# RGBS_to_YPbPr.net
KiCad netlist of a schematic drawn in EAGLE
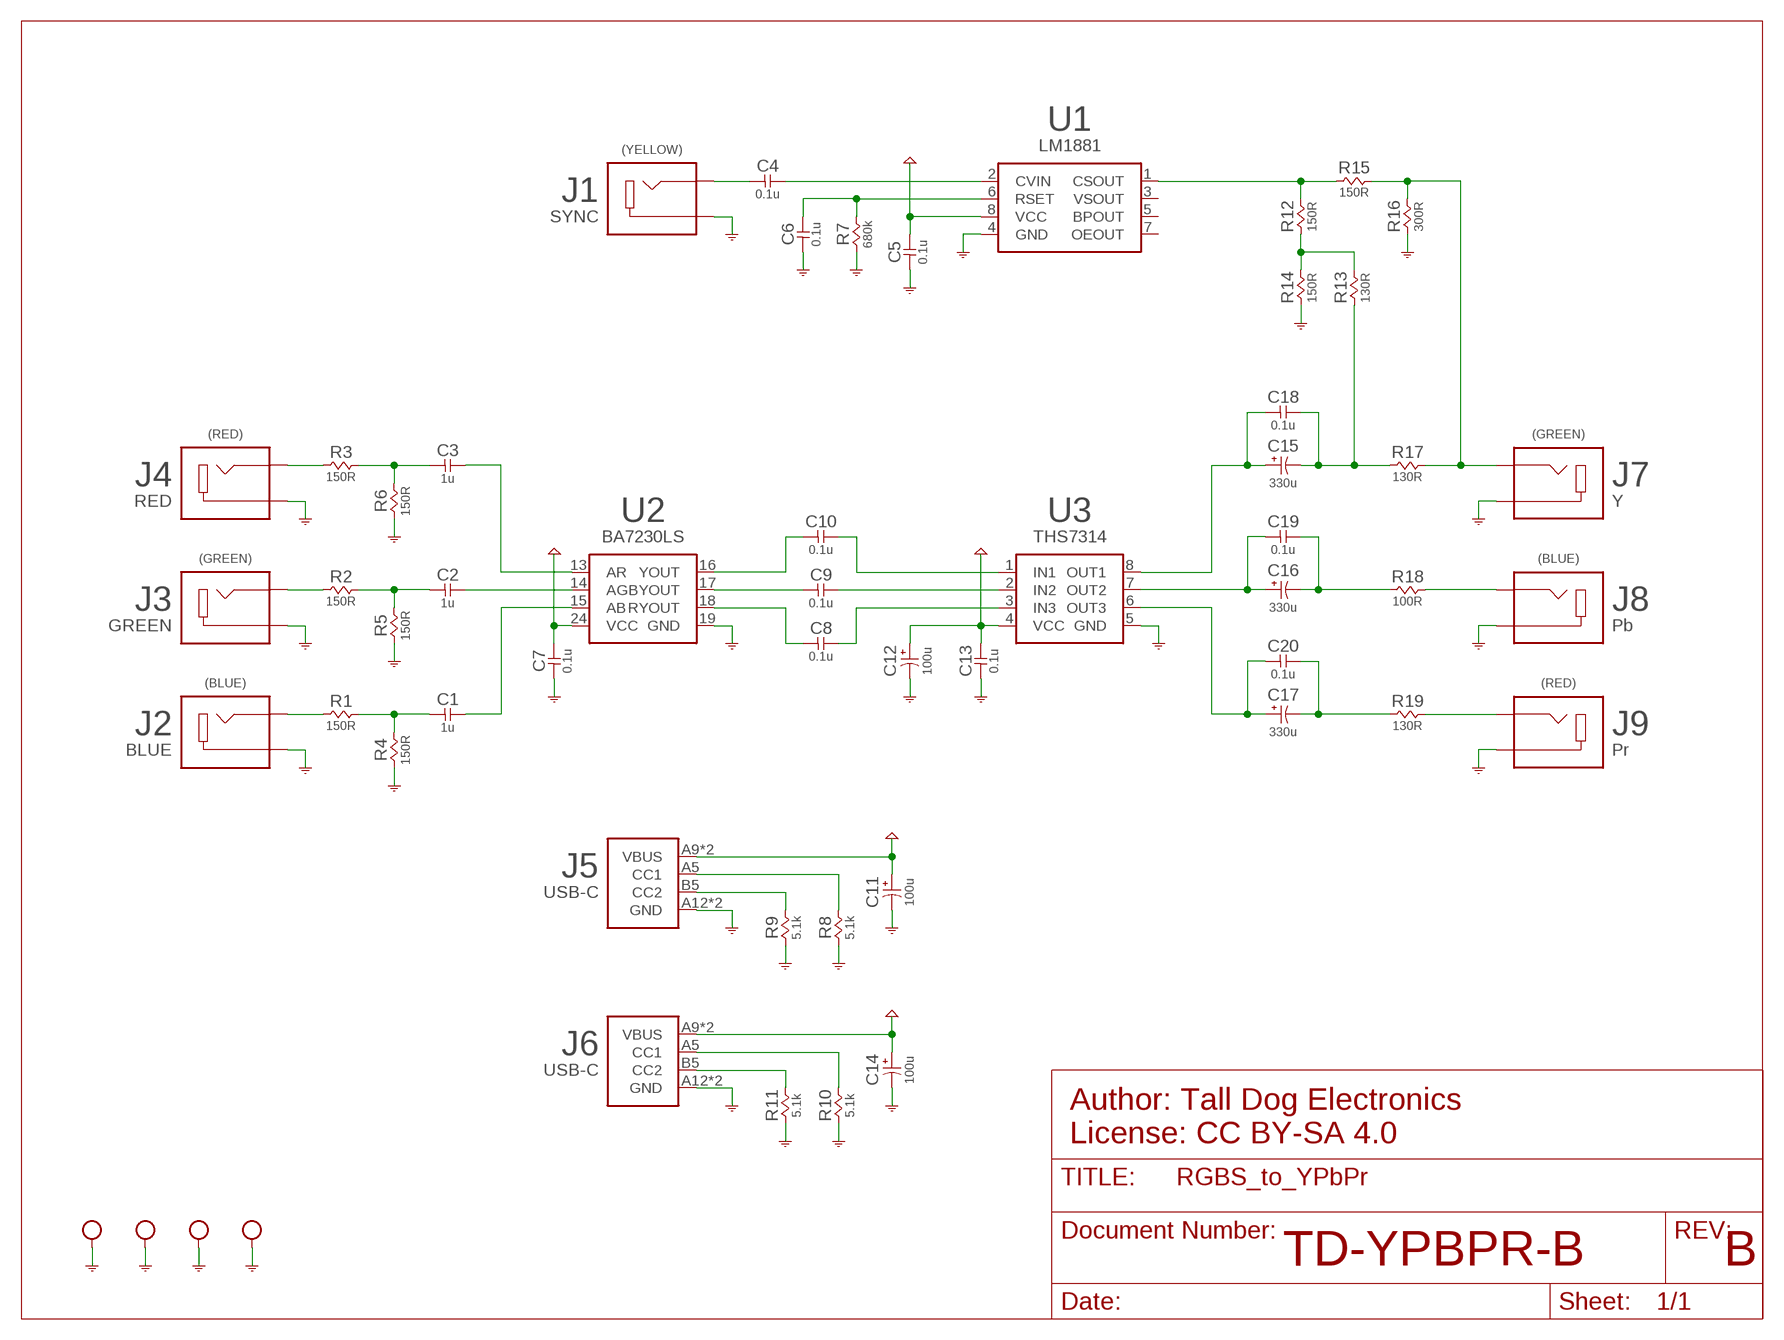
[diagram p0: schematic, sheet 1]

(export (version "E")
  (design (tool "Eeschema 10.0.6"))
  (components
    (comp (ref "C1")
      (value "1u")
      (footprint "eagle-import:0805-NP")
      (libsource (lib "eagle-import") (part "CAP-NP-0805"))
    )
    (comp (ref "C2")
      (value "1u")
      (footprint "eagle-import:0805-NP")
      (libsource (lib "eagle-import") (part "CAP-NP-0805"))
    )
    (comp (ref "C3")
      (value "1u")
      (footprint "eagle-import:0805-NP")
      (libsource (lib "eagle-import") (part "CAP-NP-0805"))
    )
    (comp (ref "C4")
      (value "0.1u")
      (footprint "eagle-import:0805-NP")
      (libsource (lib "eagle-import") (part "CAP-NP-0805"))
    )
    (comp (ref "C5")
      (value "0.1u")
      (footprint "eagle-import:0805-NP")
      (libsource (lib "eagle-import") (part "CAP-NP-0805"))
    )
    (comp (ref "C6")
      (value "0.1u")
      (footprint "eagle-import:0805-NP")
      (libsource (lib "eagle-import") (part "CAP-NP-0805"))
    )
    (comp (ref "C7")
      (value "0.1u")
      (footprint "eagle-import:0805-NP")
      (libsource (lib "eagle-import") (part "CAP-NP-0805"))
    )
    (comp (ref "C8")
      (value "0.1u")
      (footprint "eagle-import:0805-NP")
      (libsource (lib "eagle-import") (part "CAP-NP-0805"))
    )
    (comp (ref "C9")
      (value "0.1u")
      (footprint "eagle-import:0805-NP")
      (libsource (lib "eagle-import") (part "CAP-NP-0805"))
    )
    (comp (ref "C10")
      (value "0.1u")
      (footprint "eagle-import:0805-NP")
      (libsource (lib "eagle-import") (part "CAP-NP-0805"))
    )
    (comp (ref "C11")
      (value "100u")
      (footprint "eagle-import:ECAP-D")
      (libsource (lib "eagle-import") (part "CAP-P-D"))
    )
    (comp (ref "C12")
      (value "100u")
      (footprint "eagle-import:ECAP-D")
      (libsource (lib "eagle-import") (part "CAP-P-D"))
    )
    (comp (ref "C13")
      (value "0.1u")
      (footprint "eagle-import:0805-NP")
      (libsource (lib "eagle-import") (part "CAP-NP-0805"))
    )
    (comp (ref "C14")
      (value "100u")
      (footprint "eagle-import:ECAP-D")
      (libsource (lib "eagle-import") (part "CAP-P-D"))
    )
    (comp (ref "C15")
      (value "330u")
      (footprint "eagle-import:ECAP-E")
      (libsource (lib "eagle-import") (part "CAP-P-E"))
    )
    (comp (ref "C16")
      (value "330u")
      (footprint "eagle-import:ECAP-E")
      (libsource (lib "eagle-import") (part "CAP-P-E"))
    )
    (comp (ref "C17")
      (value "330u")
      (footprint "eagle-import:ECAP-E")
      (libsource (lib "eagle-import") (part "CAP-P-E"))
    )
    (comp (ref "C18")
      (value "0.1u")
      (footprint "eagle-import:0805-NP")
      (libsource (lib "eagle-import") (part "CAP-NP-0805"))
    )
    (comp (ref "C19")
      (value "0.1u")
      (footprint "eagle-import:0805-NP")
      (libsource (lib "eagle-import") (part "CAP-NP-0805"))
    )
    (comp (ref "C20")
      (value "0.1u")
      (footprint "eagle-import:0805-NP")
      (libsource (lib "eagle-import") (part "CAP-NP-0805"))
    )
    (comp (ref "HOLE1")
      (value "HOLE-M2.5")
      (footprint "eagle-import:HOLE-M2.5")
      (libsource (lib "eagle-import") (part "HOLE-M2.5"))
    )
    (comp (ref "HOLE2")
      (value "HOLE-M2.5")
      (footprint "eagle-import:HOLE-M2.5")
      (libsource (lib "eagle-import") (part "HOLE-M2.5"))
    )
    (comp (ref "HOLE3")
      (value "HOLE-M2.5")
      (footprint "eagle-import:HOLE-M2.5")
      (libsource (lib "eagle-import") (part "HOLE-M2.5"))
    )
    (comp (ref "HOLE4")
      (value "HOLE-M2.5")
      (footprint "eagle-import:HOLE-M2.5")
      (libsource (lib "eagle-import") (part "HOLE-M2.5"))
    )
    (comp (ref "J1")
      (value "SYNC")
      (footprint "eagle-import:RCJ")
      (libsource (lib "eagle-import") (part "JACK"))
    )
    (comp (ref "J2")
      (value "BLUE")
      (footprint "eagle-import:RCJ")
      (libsource (lib "eagle-import") (part "JACK"))
    )
    (comp (ref "J3")
      (value "GREEN")
      (footprint "eagle-import:RCJ")
      (libsource (lib "eagle-import") (part "JACK"))
    )
    (comp (ref "J4")
      (value "RED")
      (footprint "eagle-import:RCJ")
      (libsource (lib "eagle-import") (part "JACK"))
    )
    (comp (ref "J5")
      (value "USB-C")
      (footprint "eagle-import:USB4125")
      (libsource (lib "eagle-import") (part "USB-C-POWER"))
    )
    (comp (ref "J6")
      (value "USB-C")
      (footprint "eagle-import:USB4125")
      (libsource (lib "eagle-import") (part "USB-C-POWER"))
    )
    (comp (ref "J7")
      (value "Y")
      (footprint "eagle-import:RCJ")
      (libsource (lib "eagle-import") (part "JACK"))
    )
    (comp (ref "J8")
      (value "Pb")
      (footprint "eagle-import:RCJ")
      (libsource (lib "eagle-import") (part "JACK"))
    )
    (comp (ref "J9")
      (value "Pr")
      (footprint "eagle-import:RCJ")
      (libsource (lib "eagle-import") (part "JACK"))
    )
    (comp (ref "R1")
      (value "150R")
      (footprint "eagle-import:0805-NP")
      (libsource (lib "eagle-import") (part "RESISTOR-0805"))
    )
    (comp (ref "R2")
      (value "150R")
      (footprint "eagle-import:0805-NP")
      (libsource (lib "eagle-import") (part "RESISTOR-0805"))
    )
    (comp (ref "R3")
      (value "150R")
      (footprint "eagle-import:0805-NP")
      (libsource (lib "eagle-import") (part "RESISTOR-0805"))
    )
    (comp (ref "R4")
      (value "150R")
      (footprint "eagle-import:0805-NP")
      (libsource (lib "eagle-import") (part "RESISTOR-0805"))
    )
    (comp (ref "R5")
      (value "150R")
      (footprint "eagle-import:0805-NP")
      (libsource (lib "eagle-import") (part "RESISTOR-0805"))
    )
    (comp (ref "R6")
      (value "150R")
      (footprint "eagle-import:0805-NP")
      (libsource (lib "eagle-import") (part "RESISTOR-0805"))
    )
    (comp (ref "R7")
      (value "680k")
      (footprint "eagle-import:0805-NP")
      (libsource (lib "eagle-import") (part "RESISTOR-0805"))
    )
    (comp (ref "R8")
      (value "5.1k")
      (footprint "eagle-import:0805-NP")
      (libsource (lib "eagle-import") (part "RESISTOR-0805"))
    )
    (comp (ref "R9")
      (value "5.1k")
      (footprint "eagle-import:0805-NP")
      (libsource (lib "eagle-import") (part "RESISTOR-0805"))
    )
    (comp (ref "R10")
      (value "5.1k")
      (footprint "eagle-import:0805-NP")
      (libsource (lib "eagle-import") (part "RESISTOR-0805"))
    )
    (comp (ref "R11")
      (value "5.1k")
      (footprint "eagle-import:0805-NP")
      (libsource (lib "eagle-import") (part "RESISTOR-0805"))
    )
    (comp (ref "R12")
      (value "150R")
      (footprint "eagle-import:0805-NP")
      (libsource (lib "eagle-import") (part "RESISTOR-0805"))
    )
    (comp (ref "R13")
      (value "130R")
      (footprint "eagle-import:0805-NP")
      (libsource (lib "eagle-import") (part "RESISTOR-0805"))
    )
    (comp (ref "R14")
      (value "150R")
      (footprint "eagle-import:0805-NP")
      (libsource (lib "eagle-import") (part "RESISTOR-0805"))
    )
    (comp (ref "R15")
      (value "150R")
      (footprint "eagle-import:0805-NP")
      (libsource (lib "eagle-import") (part "RESISTOR-0805"))
    )
    (comp (ref "R16")
      (value "300R")
      (footprint "eagle-import:0805-NP")
      (libsource (lib "eagle-import") (part "RESISTOR-0805"))
    )
    (comp (ref "R17")
      (value "130R")
      (footprint "eagle-import:0805-NP")
      (libsource (lib "eagle-import") (part "RESISTOR-0805"))
    )
    (comp (ref "R18")
      (value "100R")
      (footprint "eagle-import:0805-NP")
      (libsource (lib "eagle-import") (part "RESISTOR-0805"))
    )
    (comp (ref "R19")
      (value "130R")
      (footprint "eagle-import:0805-NP")
      (libsource (lib "eagle-import") (part "RESISTOR-0805"))
    )
    (comp (ref "U1")
      (value "LM1881")
      (footprint "eagle-import:SOIC-8")
      (libsource (lib "eagle-import") (part "LM1881"))
    )
    (comp (ref "U2")
      (value "BA7230LS")
      (footprint "eagle-import:SZIP-24")
      (libsource (lib "eagle-import") (part "BA7230LS"))
    )
    (comp (ref "U3")
      (value "THS7314")
      (footprint "eagle-import:SOIC-8")
      (libsource (lib "eagle-import") (part "THS7314"))
    )
  )
  (nets
    (net (code "1") (name "GND") (class "Default")
      (node (ref "C11") (pin "C") (pinfunction "C_C") (pintype "bidirectional"))
      (node (ref "C12") (pin "C") (pinfunction "C_C") (pintype "bidirectional"))
      (node (ref "C13") (pin "1") (pinfunction "1_1") (pintype "bidirectional"))
      (node (ref "C14") (pin "C") (pinfunction "C_C") (pintype "bidirectional"))
      (node (ref "C5") (pin "1") (pinfunction "1_1") (pintype "bidirectional"))
      (node (ref "C6") (pin "1") (pinfunction "1_1") (pintype "bidirectional"))
      (node (ref "C7") (pin "1") (pinfunction "1_1") (pintype "bidirectional"))
      (node (ref "HOLE1") (pin "P$1") (pinfunction "P$1_P$1") (pintype "bidirectional"))
      (node (ref "HOLE1") (pin "P$13") (pinfunction "P$1_P$13") (pintype "bidirectional"))
      (node (ref "HOLE1") (pin "P$14") (pinfunction "P$1_P$14") (pintype "bidirectional"))
      (node (ref "HOLE1") (pin "P$15") (pinfunction "P$1_P$15") (pintype "bidirectional"))
      (node (ref "HOLE1") (pin "P$16") (pinfunction "P$1_P$16") (pintype "bidirectional"))
      (node (ref "HOLE1") (pin "P$6") (pinfunction "P$1_P$6") (pintype "bidirectional"))
      (node (ref "HOLE1") (pin "P$7") (pinfunction "P$1_P$7") (pintype "bidirectional"))
      (node (ref "HOLE1") (pin "P$8") (pinfunction "P$1_P$8") (pintype "bidirectional"))
      (node (ref "HOLE1") (pin "P$9") (pinfunction "P$1_P$9") (pintype "bidirectional"))
      (node (ref "HOLE2") (pin "P$1") (pinfunction "P$1_P$1") (pintype "bidirectional"))
      (node (ref "HOLE2") (pin "P$13") (pinfunction "P$1_P$13") (pintype "bidirectional"))
      (node (ref "HOLE2") (pin "P$14") (pinfunction "P$1_P$14") (pintype "bidirectional"))
      (node (ref "HOLE2") (pin "P$15") (pinfunction "P$1_P$15") (pintype "bidirectional"))
      (node (ref "HOLE2") (pin "P$16") (pinfunction "P$1_P$16") (pintype "bidirectional"))
      (node (ref "HOLE2") (pin "P$6") (pinfunction "P$1_P$6") (pintype "bidirectional"))
      (node (ref "HOLE2") (pin "P$7") (pinfunction "P$1_P$7") (pintype "bidirectional"))
      (node (ref "HOLE2") (pin "P$8") (pinfunction "P$1_P$8") (pintype "bidirectional"))
      (node (ref "HOLE2") (pin "P$9") (pinfunction "P$1_P$9") (pintype "bidirectional"))
      (node (ref "HOLE3") (pin "P$1") (pinfunction "P$1_P$1") (pintype "bidirectional"))
      (node (ref "HOLE3") (pin "P$13") (pinfunction "P$1_P$13") (pintype "bidirectional"))
      (node (ref "HOLE3") (pin "P$14") (pinfunction "P$1_P$14") (pintype "bidirectional"))
      (node (ref "HOLE3") (pin "P$15") (pinfunction "P$1_P$15") (pintype "bidirectional"))
      (node (ref "HOLE3") (pin "P$16") (pinfunction "P$1_P$16") (pintype "bidirectional"))
      (node (ref "HOLE3") (pin "P$6") (pinfunction "P$1_P$6") (pintype "bidirectional"))
      (node (ref "HOLE3") (pin "P$7") (pinfunction "P$1_P$7") (pintype "bidirectional"))
      (node (ref "HOLE3") (pin "P$8") (pinfunction "P$1_P$8") (pintype "bidirectional"))
      (node (ref "HOLE3") (pin "P$9") (pinfunction "P$1_P$9") (pintype "bidirectional"))
      (node (ref "HOLE4") (pin "P$1") (pinfunction "P$1_P$1") (pintype "bidirectional"))
      (node (ref "HOLE4") (pin "P$13") (pinfunction "P$1_P$13") (pintype "bidirectional"))
      (node (ref "HOLE4") (pin "P$14") (pinfunction "P$1_P$14") (pintype "bidirectional"))
      (node (ref "HOLE4") (pin "P$15") (pinfunction "P$1_P$15") (pintype "bidirectional"))
      (node (ref "HOLE4") (pin "P$16") (pinfunction "P$1_P$16") (pintype "bidirectional"))
      (node (ref "HOLE4") (pin "P$6") (pinfunction "P$1_P$6") (pintype "bidirectional"))
      (node (ref "HOLE4") (pin "P$7") (pinfunction "P$1_P$7") (pintype "bidirectional"))
      (node (ref "HOLE4") (pin "P$8") (pinfunction "P$1_P$8") (pintype "bidirectional"))
      (node (ref "HOLE4") (pin "P$9") (pinfunction "P$1_P$9") (pintype "bidirectional"))
      (node (ref "J1") (pin "1B") (pinfunction "S_1B") (pintype "bidirectional"))
      (node (ref "J1") (pin "1T") (pinfunction "S_1T") (pintype "bidirectional"))
      (node (ref "J2") (pin "1B") (pinfunction "S_1B") (pintype "bidirectional"))
      (node (ref "J2") (pin "1T") (pinfunction "S_1T") (pintype "bidirectional"))
      (node (ref "J3") (pin "1B") (pinfunction "S_1B") (pintype "bidirectional"))
      (node (ref "J3") (pin "1T") (pinfunction "S_1T") (pintype "bidirectional"))
      (node (ref "J4") (pin "1B") (pinfunction "S_1B") (pintype "bidirectional"))
      (node (ref "J4") (pin "1T") (pinfunction "S_1T") (pintype "bidirectional"))
      (node (ref "J5") (pin "A12") (pinfunction "GND_A12") (pintype "bidirectional"))
      (node (ref "J5") (pin "B12") (pinfunction "GND_B12") (pintype "bidirectional"))
      (node (ref "J6") (pin "A12") (pinfunction "GND_A12") (pintype "bidirectional"))
      (node (ref "J6") (pin "B12") (pinfunction "GND_B12") (pintype "bidirectional"))
      (node (ref "J7") (pin "1B") (pinfunction "S_1B") (pintype "bidirectional"))
      (node (ref "J7") (pin "1T") (pinfunction "S_1T") (pintype "bidirectional"))
      (node (ref "J8") (pin "1B") (pinfunction "S_1B") (pintype "bidirectional"))
      (node (ref "J8") (pin "1T") (pinfunction "S_1T") (pintype "bidirectional"))
      (node (ref "J9") (pin "1B") (pinfunction "S_1B") (pintype "bidirectional"))
      (node (ref "J9") (pin "1T") (pinfunction "S_1T") (pintype "bidirectional"))
      (node (ref "R10") (pin "1") (pinfunction "1_1") (pintype "bidirectional"))
      (node (ref "R11") (pin "1") (pinfunction "1_1") (pintype "bidirectional"))
      (node (ref "R14") (pin "1") (pinfunction "1_1") (pintype "bidirectional"))
      (node (ref "R16") (pin "1") (pinfunction "1_1") (pintype "bidirectional"))
      (node (ref "R4") (pin "1") (pinfunction "1_1") (pintype "bidirectional"))
      (node (ref "R5") (pin "1") (pinfunction "1_1") (pintype "bidirectional"))
      (node (ref "R6") (pin "1") (pinfunction "1_1") (pintype "bidirectional"))
      (node (ref "R7") (pin "1") (pinfunction "1_1") (pintype "bidirectional"))
      (node (ref "R8") (pin "1") (pinfunction "1_1") (pintype "bidirectional"))
      (node (ref "R9") (pin "1") (pinfunction "1_1") (pintype "bidirectional"))
      (node (ref "U1") (pin "4") (pinfunction "GND_4") (pintype "bidirectional"))
      (node (ref "U2") (pin "19") (pinfunction "GND_19") (pintype "bidirectional"))
      (node (ref "U3") (pin "5") (pinfunction "GND_5") (pintype "bidirectional"))
    )
    (net (code "2") (name "Net-(C1-Pad1)") (class "Default")
      (node (ref "C1") (pin "1") (pinfunction "1_1") (pintype "bidirectional"))
      (node (ref "R1") (pin "2") (pinfunction "2_2") (pintype "bidirectional"))
      (node (ref "R4") (pin "2") (pinfunction "2_2") (pintype "bidirectional"))
    )
    (net (code "3") (name "Net-(C2-Pad1)") (class "Default")
      (node (ref "C2") (pin "1") (pinfunction "1_1") (pintype "bidirectional"))
      (node (ref "R2") (pin "2") (pinfunction "2_2") (pintype "bidirectional"))
      (node (ref "R5") (pin "2") (pinfunction "2_2") (pintype "bidirectional"))
    )
    (net (code "4") (name "Net-(C3-Pad1)") (class "Default")
      (node (ref "C3") (pin "1") (pinfunction "1_1") (pintype "bidirectional"))
      (node (ref "R3") (pin "2") (pinfunction "2_2") (pintype "bidirectional"))
      (node (ref "R6") (pin "2") (pinfunction "2_2") (pintype "bidirectional"))
    )
    (net (code "5") (name "Net-(C4-Pad1)") (class "Default")
      (node (ref "C4") (pin "1") (pinfunction "1_1") (pintype "bidirectional"))
      (node (ref "J1") (pin "2B") (pinfunction "T_2B") (pintype "bidirectional"))
      (node (ref "J1") (pin "2T") (pinfunction "T_2T") (pintype "bidirectional"))
    )
    (net (code "6") (name "Net-(C15-PadC)") (class "Default")
      (node (ref "C15") (pin "C") (pinfunction "C_C") (pintype "bidirectional"))
      (node (ref "C18") (pin "2") (pinfunction "2_2") (pintype "bidirectional"))
      (node (ref "R13") (pin "1") (pinfunction "1_1") (pintype "bidirectional"))
      (node (ref "R17") (pin "1") (pinfunction "1_1") (pintype "bidirectional"))
    )
    (net (code "7") (name "Net-(C16-PadC)") (class "Default")
      (node (ref "C16") (pin "C") (pinfunction "C_C") (pintype "bidirectional"))
      (node (ref "C19") (pin "2") (pinfunction "2_2") (pintype "bidirectional"))
      (node (ref "R18") (pin "1") (pinfunction "1_1") (pintype "bidirectional"))
    )
    (net (code "8") (name "Net-(C17-PadC)") (class "Default")
      (node (ref "C17") (pin "C") (pinfunction "C_C") (pintype "bidirectional"))
      (node (ref "C20") (pin "2") (pinfunction "2_2") (pintype "bidirectional"))
      (node (ref "R19") (pin "1") (pinfunction "1_1") (pintype "bidirectional"))
    )
    (net (code "9") (name "Net-(J2-T-Pad2B)") (class "Default")
      (node (ref "J2") (pin "2B") (pinfunction "T_2B") (pintype "bidirectional"))
      (node (ref "J2") (pin "2T") (pinfunction "T_2T") (pintype "bidirectional"))
      (node (ref "R1") (pin "1") (pinfunction "1_1") (pintype "bidirectional"))
    )
    (net (code "10") (name "Net-(J3-T-Pad2B)") (class "Default")
      (node (ref "J3") (pin "2B") (pinfunction "T_2B") (pintype "bidirectional"))
      (node (ref "J3") (pin "2T") (pinfunction "T_2T") (pintype "bidirectional"))
      (node (ref "R2") (pin "1") (pinfunction "1_1") (pintype "bidirectional"))
    )
    (net (code "11") (name "Net-(J4-T-Pad2B)") (class "Default")
      (node (ref "J4") (pin "2B") (pinfunction "T_2B") (pintype "bidirectional"))
      (node (ref "J4") (pin "2T") (pinfunction "T_2T") (pintype "bidirectional"))
      (node (ref "R3") (pin "1") (pinfunction "1_1") (pintype "bidirectional"))
    )
    (net (code "12") (name "Net-(J5-CC1)") (class "Default")
      (node (ref "J5") (pin "A5") (pinfunction "CC1_A5") (pintype "bidirectional"))
      (node (ref "R8") (pin "2") (pinfunction "2_2") (pintype "bidirectional"))
    )
    (net (code "13") (name "Net-(J5-CC2)") (class "Default")
      (node (ref "J5") (pin "B5") (pinfunction "CC2_B5") (pintype "bidirectional"))
      (node (ref "R9") (pin "2") (pinfunction "2_2") (pintype "bidirectional"))
    )
    (net (code "14") (name "Net-(J6-CC1)") (class "Default")
      (node (ref "J6") (pin "A5") (pinfunction "CC1_A5") (pintype "bidirectional"))
      (node (ref "R10") (pin "2") (pinfunction "2_2") (pintype "bidirectional"))
    )
    (net (code "15") (name "Net-(J6-CC2)") (class "Default")
      (node (ref "J6") (pin "B5") (pinfunction "CC2_B5") (pintype "bidirectional"))
      (node (ref "R11") (pin "2") (pinfunction "2_2") (pintype "bidirectional"))
    )
    (net (code "16") (name "Net-(J7-T-Pad2B)") (class "Default")
      (node (ref "J7") (pin "2B") (pinfunction "T_2B") (pintype "bidirectional"))
      (node (ref "J7") (pin "2T") (pinfunction "T_2T") (pintype "bidirectional"))
      (node (ref "R15") (pin "2") (pinfunction "2_2") (pintype "bidirectional"))
      (node (ref "R16") (pin "2") (pinfunction "2_2") (pintype "bidirectional"))
      (node (ref "R17") (pin "2") (pinfunction "2_2") (pintype "bidirectional"))
    )
    (net (code "17") (name "Net-(J8-T-Pad2B)") (class "Default")
      (node (ref "J8") (pin "2B") (pinfunction "T_2B") (pintype "bidirectional"))
      (node (ref "J8") (pin "2T") (pinfunction "T_2T") (pintype "bidirectional"))
      (node (ref "R18") (pin "2") (pinfunction "2_2") (pintype "bidirectional"))
    )
    (net (code "18") (name "Net-(J9-T-Pad2B)") (class "Default")
      (node (ref "J9") (pin "2B") (pinfunction "T_2B") (pintype "bidirectional"))
      (node (ref "J9") (pin "2T") (pinfunction "T_2T") (pintype "bidirectional"))
      (node (ref "R19") (pin "2") (pinfunction "2_2") (pintype "bidirectional"))
    )
    (net (code "19") (name "Net-(R12-Pad1)") (class "Default")
      (node (ref "R12") (pin "1") (pinfunction "1_1") (pintype "bidirectional"))
      (node (ref "R13") (pin "2") (pinfunction "2_2") (pintype "bidirectional"))
      (node (ref "R14") (pin "2") (pinfunction "2_2") (pintype "bidirectional"))
    )
    (net (code "20") (name "Net-(U1-CSOUT)") (class "Default")
      (node (ref "R12") (pin "2") (pinfunction "2_2") (pintype "bidirectional"))
      (node (ref "R15") (pin "1") (pinfunction "1_1") (pintype "bidirectional"))
      (node (ref "U1") (pin "1") (pinfunction "CSOUT_1") (pintype "bidirectional"))
    )
    (net (code "21") (name "Net-(U1-CVIN)") (class "Default")
      (node (ref "C4") (pin "2") (pinfunction "2_2") (pintype "bidirectional"))
      (node (ref "U1") (pin "2") (pinfunction "CVIN_2") (pintype "bidirectional"))
    )
    (net (code "22") (name "Net-(U1-RSET)") (class "Default")
      (node (ref "C6") (pin "2") (pinfunction "2_2") (pintype "bidirectional"))
      (node (ref "R7") (pin "2") (pinfunction "2_2") (pintype "bidirectional"))
      (node (ref "U1") (pin "6") (pinfunction "RSET_6") (pintype "bidirectional"))
    )
    (net (code "23") (name "Net-(U2-AB)") (class "Default")
      (node (ref "C1") (pin "2") (pinfunction "2_2") (pintype "bidirectional"))
      (node (ref "U2") (pin "15") (pinfunction "AB_15") (pintype "bidirectional"))
    )
    (net (code "24") (name "Net-(U2-AG)") (class "Default")
      (node (ref "C2") (pin "2") (pinfunction "2_2") (pintype "bidirectional"))
      (node (ref "U2") (pin "14") (pinfunction "AG_14") (pintype "bidirectional"))
    )
    (net (code "25") (name "Net-(U2-AR)") (class "Default")
      (node (ref "C3") (pin "2") (pinfunction "2_2") (pintype "bidirectional"))
      (node (ref "U2") (pin "13") (pinfunction "AR_13") (pintype "bidirectional"))
    )
    (net (code "26") (name "Net-(U2-BYOUT)") (class "Default")
      (node (ref "C9") (pin "1") (pinfunction "1_1") (pintype "bidirectional"))
      (node (ref "U2") (pin "17") (pinfunction "BYOUT_17") (pintype "bidirectional"))
    )
    (net (code "27") (name "Net-(U2-RYOUT)") (class "Default")
      (node (ref "C8") (pin "1") (pinfunction "1_1") (pintype "bidirectional"))
      (node (ref "U2") (pin "18") (pinfunction "RYOUT_18") (pintype "bidirectional"))
    )
    (net (code "28") (name "Net-(U2-YOUT)") (class "Default")
      (node (ref "C10") (pin "1") (pinfunction "1_1") (pintype "bidirectional"))
      (node (ref "U2") (pin "16") (pinfunction "YOUT_16") (pintype "bidirectional"))
    )
    (net (code "29") (name "Net-(U3-IN1)") (class "Default")
      (node (ref "C10") (pin "2") (pinfunction "2_2") (pintype "bidirectional"))
      (node (ref "U3") (pin "1") (pinfunction "IN1_1") (pintype "bidirectional"))
    )
    (net (code "30") (name "Net-(U3-IN2)") (class "Default")
      (node (ref "C9") (pin "2") (pinfunction "2_2") (pintype "bidirectional"))
      (node (ref "U3") (pin "2") (pinfunction "IN2_2") (pintype "bidirectional"))
    )
    (net (code "31") (name "Net-(U3-IN3)") (class "Default")
      (node (ref "C8") (pin "2") (pinfunction "2_2") (pintype "bidirectional"))
      (node (ref "U3") (pin "3") (pinfunction "IN3_3") (pintype "bidirectional"))
    )
    (net (code "32") (name "Net-(U3-OUT1)") (class "Default")
      (node (ref "C15") (pin "A") (pinfunction "A_A") (pintype "bidirectional"))
      (node (ref "C18") (pin "1") (pinfunction "1_1") (pintype "bidirectional"))
      (node (ref "U3") (pin "8") (pinfunction "OUT1_8") (pintype "bidirectional"))
    )
    (net (code "33") (name "Net-(U3-OUT2)") (class "Default")
      (node (ref "C16") (pin "A") (pinfunction "A_A") (pintype "bidirectional"))
      (node (ref "C19") (pin "1") (pinfunction "1_1") (pintype "bidirectional"))
      (node (ref "U3") (pin "7") (pinfunction "OUT2_7") (pintype "bidirectional"))
    )
    (net (code "34") (name "Net-(U3-OUT3)") (class "Default")
      (node (ref "C17") (pin "A") (pinfunction "A_A") (pintype "bidirectional"))
      (node (ref "C20") (pin "1") (pinfunction "1_1") (pintype "bidirectional"))
      (node (ref "U3") (pin "6") (pinfunction "OUT3_6") (pintype "bidirectional"))
    )
    (net (code "35") (name "VCC") (class "Default")
      (node (ref "C11") (pin "A") (pinfunction "A_A") (pintype "bidirectional"))
      (node (ref "C12") (pin "A") (pinfunction "A_A") (pintype "bidirectional"))
      (node (ref "C13") (pin "2") (pinfunction "2_2") (pintype "bidirectional"))
      (node (ref "C14") (pin "A") (pinfunction "A_A") (pintype "bidirectional"))
      (node (ref "C5") (pin "2") (pinfunction "2_2") (pintype "bidirectional"))
      (node (ref "C7") (pin "2") (pinfunction "2_2") (pintype "bidirectional"))
      (node (ref "J5") (pin "A9") (pinfunction "VBUS_A9") (pintype "bidirectional"))
      (node (ref "J5") (pin "B9") (pinfunction "VBUS_B9") (pintype "bidirectional"))
      (node (ref "J6") (pin "A9") (pinfunction "VBUS_A9") (pintype "bidirectional"))
      (node (ref "J6") (pin "B9") (pinfunction "VBUS_B9") (pintype "bidirectional"))
      (node (ref "U1") (pin "8") (pinfunction "VCC_8") (pintype "bidirectional"))
      (node (ref "U2") (pin "24") (pinfunction "VCC_24") (pintype "bidirectional"))
      (node (ref "U3") (pin "4") (pinfunction "VCC_4") (pintype "bidirectional"))
    )
    (net (code "36") (name "unconnected-(U1-BPOUT-Pad5)") (class "Default")
      (node (ref "U1") (pin "5") (pinfunction "BPOUT_5") (pintype "bidirectional"))
    )
    (net (code "37") (name "unconnected-(U1-OEOUT-Pad7)") (class "Default")
      (node (ref "U1") (pin "7") (pinfunction "OEOUT_7") (pintype "bidirectional"))
    )
    (net (code "38") (name "unconnected-(U1-VSOUT-Pad3)") (class "Default")
      (node (ref "U1") (pin "3") (pinfunction "VSOUT_3") (pintype "bidirectional"))
    )
  )
)
